# Sheet1.net
KiCad netlist of a schematic drawn in Altium Designer
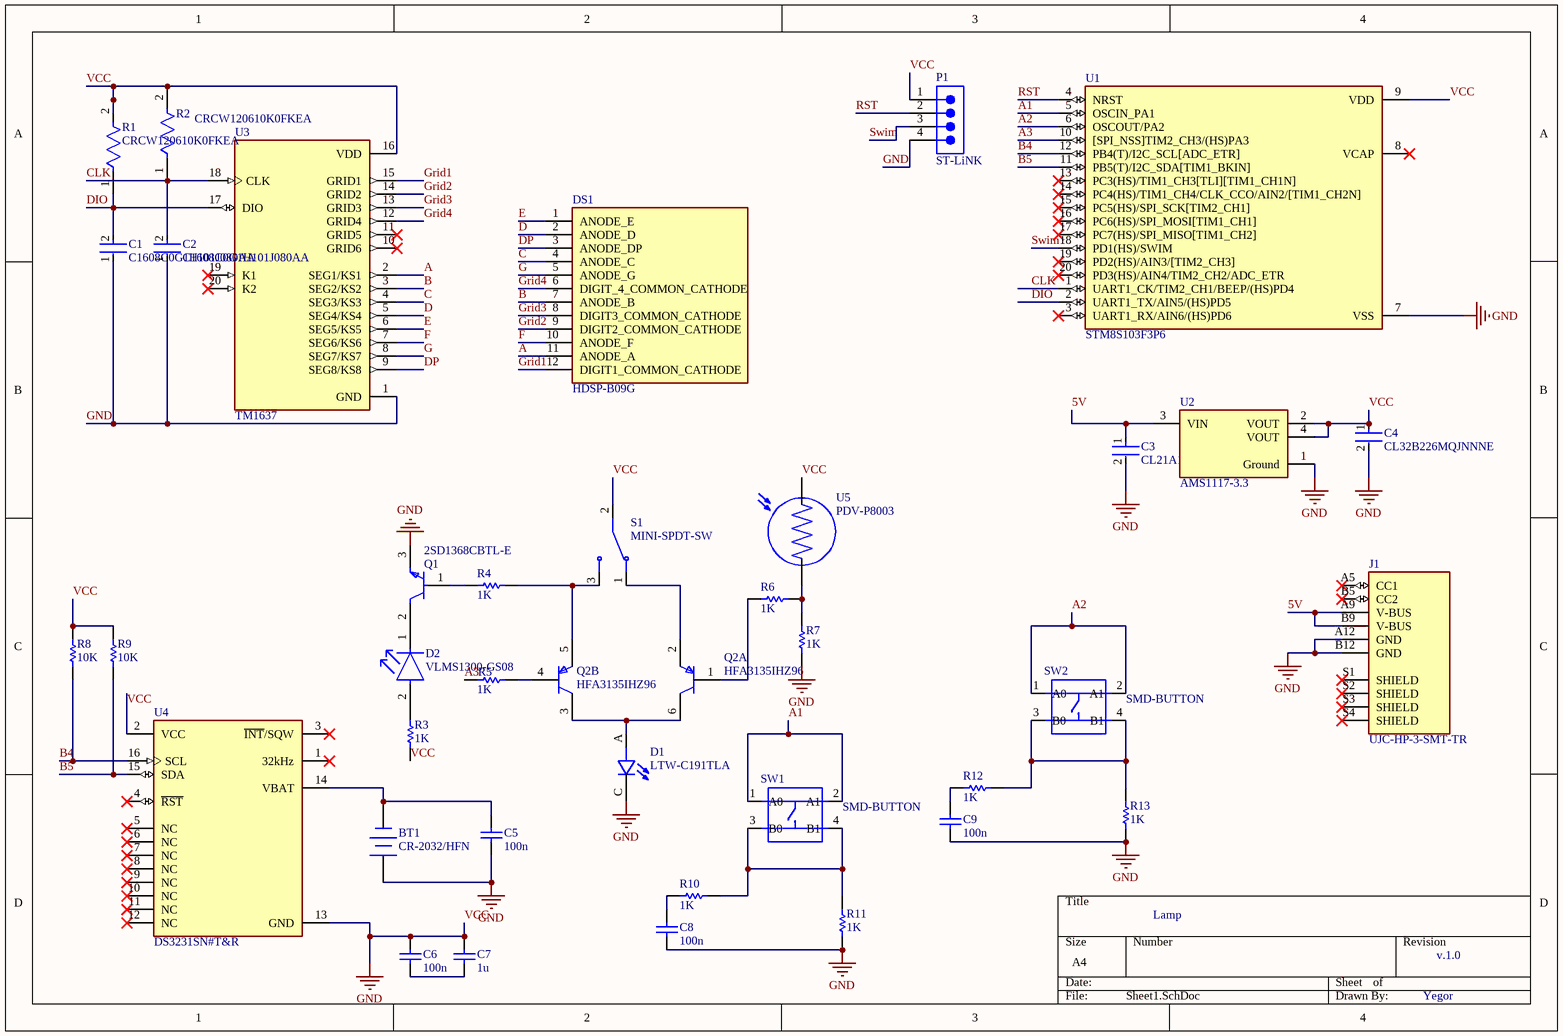
[diagram p0: Sheet1.SchDoc]

(export (version "E")
  (design (tool "Eeschema 10.0.6"))
  (components
    (comp (ref "BT1")
      (value "CR-2032/HFN")
      (footprint "PANA-CR-2032HFN")
      (description "Coin Cell Battery, 225 mAh, 0.2 mA, 3 V, -30 to 60 degC, Bulk")
      (fields (field (name "MANUFACTURER") "Panasonic"))
      (libsource (lib "Components - 25.08.25 - 13.52") (part "CMP-2000-05296-1"))
    )
    (comp (ref "C1")
      (value "C1608C0G1H101J080AA")
      (footprint "FP-C1608-080-0_1-MFG")
      (description "Multilayer Ceramic Capacitors 100pF ±5% 50V C0G SMD 0603")
      (fields (field (name "VOLTAGE") "50V") (field (name "TOLERANCE") "5%"))
      (libsource (lib "Components - 25.08.25 - 11.32") (part "CMP-08246-002637-1"))
    )
    (comp (ref "C2")
      (value "C1608C0G1H101J080AA")
      (footprint "FP-C1608-080-0_1-MFG")
      (description "Multilayer Ceramic Capacitors 100pF ±5% 50V C0G SMD 0603")
      (fields (field (name "VOLTAGE") "50V") (field (name "TOLERANCE") "5%"))
      (libsource (lib "Components - 25.08.25 - 11.32") (part "CMP-08246-002637-1"))
    )
    (comp (ref "C3")
      (value "CL21A106MPFNNNF")
      (footprint "FP-CL21-IPC_A")
      (description "CL21 Series 0805 10uF 10V ±20% Tolerance X5R Multilayer Ceramic Chip Capacitor")
      (fields (field (name "TOLERANCE") "20%"))
      (libsource (lib "Components - 25.08.25 - 12.18") (part "CMP-13271-002245-1"))
    )
    (comp (ref "C4")
      (value "CL32B226MQJNNNE")
      (footprint "FP-CL32-IPC_A")
      (description "Cap Ceramic 22uF 6.3V X7R ±20% SMD 1210 +125°C Embossed T/R")
      (fields (field (name "TOLERANCE") "20%"))
      (libsource (lib "Components - 25.08.25 - 12.17") (part "CMP-13271-001877-1"))
    )
    (comp (ref "C5")
      (value "100n")
      (description "Capacitor")
      (libsource (lib "Simulation Generic Components") (part "Capacitor"))
    )
    (comp (ref "C6")
      (value "100n")
      (description "Capacitor")
      (libsource (lib "Simulation Generic Components") (part "Capacitor"))
    )
    (comp (ref "C7")
      (value "1u")
      (description "Capacitor")
      (libsource (lib "Simulation Generic Components") (part "Capacitor"))
    )
    (comp (ref "C8")
      (value "100n")
      (description "Capacitor")
      (libsource (lib "Simulation Generic Components") (part "Capacitor"))
    )
    (comp (ref "C9")
      (value "100n")
      (description "Capacitor")
      (libsource (lib "Simulation Generic Components") (part "Capacitor"))
    )
    (comp (ref "D1")
      (value "LTW-C191TLA")
      (footprint "LEDC1608X65N")
      (description "CHIP LED WHITE 0603 TOP VIEW")
      (libsource (lib "LTW-C191TLA") (part "LTW-C191TLA"))
    )
    (comp (ref "D2")
      (value "VLMS1300-GS08")
      (footprint "FP-6_541-5092_01-4-MFG")
      (description "LED RED 0603 SMD")
      (fields
        (field (name "MANUFACTURER") "Vishay")
        (field (name "OCTOPART") "https://octopart.com/vlms1300-gs08-vishay-21709201")
      )
      (libsource (lib "Components - 25.08.25 - 21.29") (part "CMP-02520-000012-1"))
    )
    (comp (ref "DS1")
      (value "HDSP-B09G")
      (footprint "AVAGO_HDSP-B09G")
      (fields (field (name "MF") "Broadcom / Avago"))
      (libsource (lib "HDSP-B09G") (part "HDSP-B09G"))
    )
    (comp (ref "J1")
      (value "UJC-HP-3-SMT-TR")
      (footprint "CUI_UJC-HP-3-SMT-TR")
      (libsource (lib "UJC-HP-3-SMT-TR") (part "UJC-HP-3-SMT-TR"))
    )
    (comp (ref "P1")
      (value "ST-LiNK")
      (footprint "61300411021")
      (libsource (lib "Components - 25.08.25 - 11.48") (part "CMP-1502-01063-3"))
    )
    (comp (ref "Q1")
      (value "2SD1368CBTL-E")
      (footprint "PLZZ0004CA-A_MFG")
      (description "Trans GP BJT NPN 50V 1A 4-Pin(3+Tab) UPAK T/R")
      (libsource (lib "Components - 25.08.25 - 21.28") (part "CMP-00572-18697870-1"))
    )
    (comp (ref "Q2")
      (value "HFA3135IHZ96")
      (footprint "SOT95P280X145-6_P6_064_N")
      (description "Transistor, Bjt, Pair, Pnp, 11V V(Br)Ceo, 14Ma I(C), So")
      (libsource (lib "Components - 25.08.25 - 12.53") (part "CMP-00572-88253858-3"))
    )
    (comp (ref "R1")
      (value "CRCW120610K0FKEA")
      (footprint "FP-CRCW1206-e3-IPC_B")
      (description "RES Thick Film, 10kΩ, 1%, 0.25W, 100ppm/°C, 1206")
      (fields (field (name "TOLERANCE") "1%"))
      (libsource (lib "Components - 25.08.25 - 11.27") (part "CMP-2003-04807-2"))
    )
    (comp (ref "R2")
      (value "CRCW120610K0FKEA")
      (footprint "FP-CRCW1206-e3-IPC_B")
      (description "RES Thick Film, 10kΩ, 1%, 0.25W, 100ppm/°C, 1206")
      (fields (field (name "TOLERANCE") "1%"))
      (libsource (lib "Components - 25.08.25 - 11.27") (part "CMP-2003-04807-2"))
    )
    (comp (ref "R3")
      (value "1K")
      (description "Resistor")
      (libsource (lib "Simulation Generic Components") (part "Resistor"))
    )
    (comp (ref "R4")
      (value "1K")
      (description "Resistor")
      (libsource (lib "Simulation Generic Components") (part "Resistor"))
    )
    (comp (ref "R5")
      (value "1K")
      (description "Resistor")
      (libsource (lib "Simulation Generic Components") (part "Resistor"))
    )
    (comp (ref "R6")
      (value "1K")
      (description "Resistor")
      (libsource (lib "Simulation Generic Components") (part "Resistor"))
    )
    (comp (ref "R7")
      (value "1K")
      (description "Resistor")
      (libsource (lib "Simulation Generic Components") (part "Resistor"))
    )
    (comp (ref "R8")
      (value "10K")
      (description "Resistor")
      (libsource (lib "Simulation Generic Components") (part "Resistor"))
    )
    (comp (ref "R9")
      (value "10K")
      (description "Resistor")
      (libsource (lib "Simulation Generic Components") (part "Resistor"))
    )
    (comp (ref "R10")
      (value "1K")
      (description "Resistor")
      (libsource (lib "Simulation Generic Components") (part "Resistor"))
    )
    (comp (ref "R11")
      (value "1K")
      (description "Resistor")
      (libsource (lib "Simulation Generic Components") (part "Resistor"))
    )
    (comp (ref "R12")
      (value "1K")
      (description "Resistor")
      (libsource (lib "Simulation Generic Components") (part "Resistor"))
    )
    (comp (ref "R13")
      (value "1K")
      (description "Resistor")
      (libsource (lib "Simulation Generic Components") (part "Resistor"))
    )
    (comp (ref "S1")
      (value "MINI-SPDT-SW")
      (footprint "SW_MINI-SPDT-SW")
      (libsource (lib "MINI-SPDT-SW") (part "MINI-SPDT-SW"))
    )
    (comp (ref "SW1")
      (value "SMD-BUTTON")
      (footprint "SW4-SMD-5.2X5.2X1.5MM")
      (description "Switch Tactile N.O. SPST Button Gull Wing 0.05A 12VDC 3.43N SMD T/R")
      (fields (field (name "MF") "ALPS") (field (name "MP") "SKQGAKE010"))
      (libsource (lib "SMD-BUTTON_4P-5.2X5.2X1.5MM-SKQGAKE010_") (part "SMD-BUTTON(4P-5.2X5.2X1.5MM-SKQGAKE010)"))
    )
    (comp (ref "SW2")
      (value "SMD-BUTTON")
      (footprint "SW4-SMD-5.2X5.2X1.5MM")
      (description "Switch Tactile N.O. SPST Button Gull Wing 0.05A 12VDC 3.43N SMD T/R")
      (fields (field (name "MF") "ALPS") (field (name "MP") "SKQGAKE010"))
      (libsource (lib "SMD-BUTTON_4P-5.2X5.2X1.5MM-SKQGAKE010_") (part "SMD-BUTTON(4P-5.2X5.2X1.5MM-SKQGAKE010)"))
    )
    (comp (ref "U1")
      (value "STM8S103F3P6")
      (footprint "SOP65P640X120-20N")
      (description "STM8 series Microcontroller IC 8-Bit 16MHz 8KB (8K x 8) FLASH 20-TSSOP")
      (fields (field (name "MF") "STMicroelectronics"))
      (libsource (lib "STM8S103F3P6") (part "STM8S103F3P6"))
    )
    (comp (ref "U2")
      (value "AMS1117-3.3")
      (footprint "FP-AMS1117-IPC_A")
      (description "LDO Voltage Regulators 1A, 3.3V")
      (fields
        (field (name "OCTOPART") "https://octopart.com/ams1117-3.3-advanced+monolithic+systems-25899300")
        (field (name "MANUFACTURER") "Advanced Monolithic Systems")
      )
      (libsource (lib "Components - 25.08.25 - 12.03") (part "CMP-209535-000001-1"))
    )
    (comp (ref "U3")
      (value "TM1637")
      (footprint "DIP778W43P254L2612H431Q20N")
      (description "LED Drive Control Special Circuit")
      (fields (field (name "MF") "Titan Micro Electronics"))
      (libsource (lib "TM1637") (part "TM1637"))
    )
    (comp (ref "U4")
      (value "DS3231SN#T&R")
      (footprint "FP-W16-H2-MFG")
      (description "IC RTC CLK/CALENDAR I2C 16-SOIC")
      (libsource (lib "Components - 25.08.25 - 13.49") (part "CMP-0254-00375-2"))
    )
    (comp (ref "U5")
      (value "PDV-P8003")
      (footprint "XDCR_PDV-P8003")
      (description "CdS Cells 520nm 16 ~ 33kOhms @ 10 lux")
      (fields (field (name "MF") "Advanced Photonix"))
      (libsource (lib "PDV-P8003") (part "PDV-P8003"))
    )
  )
  (nets
    (net (code "1") (name "/5V") (class "Default")
      (node (ref "C3") (pin "1") (pinfunction "1_1") (pintype "passive"))
      (node (ref "J1") (pin "A9") (pinfunction "V-BUS_A9") (pintype "power_in"))
      (node (ref "J1") (pin "B9") (pinfunction "V-BUS_B9") (pintype "power_in"))
      (node (ref "U2") (pin "3") (pinfunction "VIN_3") (pintype "power_in"))
    )
    (net (code "2") (name "/A") (class "Default")
      (node (ref "DS1") (pin "11") (pinfunction "ANODE_A_11") (pintype "passive"))
      (node (ref "U3") (pin "2") (pinfunction "SEG1/KS1_2") (pintype "output"))
    )
    (net (code "3") (name "/A1") (class "Default")
      (node (ref "SW1") (pin "1") (pinfunction "A0_1") (pintype "bidirectional"))
      (node (ref "SW1") (pin "2") (pinfunction "A1_2") (pintype "bidirectional"))
      (node (ref "U1") (pin "5") (pinfunction "OSCIN_PA1_5") (pintype "bidirectional"))
    )
    (net (code "4") (name "/A2") (class "Default")
      (node (ref "SW2") (pin "1") (pinfunction "A0_1") (pintype "bidirectional"))
      (node (ref "SW2") (pin "2") (pinfunction "A1_2") (pintype "bidirectional"))
      (node (ref "U1") (pin "6") (pinfunction "OSCOUT/PA2_6") (pintype "bidirectional"))
    )
    (net (code "5") (name "/A3") (class "Default")
      (node (ref "R5") (pin "2") (pinfunction "2_2") (pintype "passive"))
      (node (ref "U1") (pin "10") (pinfunction "[SPI_NSS]TIM2_CH3/(HS)PA3_10") (pintype "bidirectional"))
    )
    (net (code "6") (name "/B") (class "Default")
      (node (ref "DS1") (pin "7") (pinfunction "ANODE_B_7") (pintype "passive"))
      (node (ref "U3") (pin "3") (pinfunction "SEG2/KS2_3") (pintype "output"))
    )
    (net (code "7") (name "/B4") (class "Default")
      (node (ref "R8") (pin "1") (pinfunction "1_1") (pintype "passive"))
      (node (ref "U1") (pin "12") (pinfunction "PB4(T)/I2C_SCL[ADC_ETR]_12") (pintype "bidirectional"))
      (node (ref "U4") (pin "16") (pinfunction "SCL_16") (pintype "input"))
    )
    (net (code "8") (name "/B5") (class "Default")
      (node (ref "R9") (pin "1") (pinfunction "1_1") (pintype "passive"))
      (node (ref "U1") (pin "11") (pinfunction "PB5(T)/I2C_SDA[TIM1_BKIN]_11") (pintype "bidirectional"))
      (node (ref "U4") (pin "15") (pinfunction "SDA_15") (pintype "bidirectional"))
    )
    (net (code "9") (name "/C") (class "Default")
      (node (ref "DS1") (pin "4") (pinfunction "ANODE_C_4") (pintype "passive"))
      (node (ref "U3") (pin "4") (pinfunction "SEG3/KS3_4") (pintype "output"))
    )
    (net (code "10") (name "/CLK") (class "Default")
      (node (ref "C2") (pin "2") (pinfunction "2_2") (pintype "passive"))
      (node (ref "R2") (pin "1") (pinfunction "1_1") (pintype "passive"))
      (node (ref "U1") (pin "1") (pinfunction "UART1_CK/TIM2_CH1/BEEP/(HS)PD4_1") (pintype "bidirectional"))
      (node (ref "U3") (pin "18") (pinfunction "CLK_18") (pintype "input"))
    )
    (net (code "11") (name "/D") (class "Default")
      (node (ref "DS1") (pin "2") (pinfunction "ANODE_D_2") (pintype "passive"))
      (node (ref "U3") (pin "5") (pinfunction "SEG4/KS4_5") (pintype "output"))
    )
    (net (code "12") (name "/DIO") (class "Default")
      (node (ref "C1") (pin "2") (pinfunction "2_2") (pintype "passive"))
      (node (ref "R1") (pin "1") (pinfunction "1_1") (pintype "passive"))
      (node (ref "U1") (pin "2") (pinfunction "UART1_TX/AIN5/(HS)PD5_2") (pintype "bidirectional"))
      (node (ref "U3") (pin "17") (pinfunction "DIO_17") (pintype "bidirectional"))
    )
    (net (code "13") (name "/DP") (class "Default")
      (node (ref "DS1") (pin "3") (pinfunction "ANODE_DP_3") (pintype "passive"))
      (node (ref "U3") (pin "9") (pinfunction "SEG8/KS8_9") (pintype "output"))
    )
    (net (code "14") (name "/E") (class "Default")
      (node (ref "DS1") (pin "1") (pinfunction "ANODE_E_1") (pintype "passive"))
      (node (ref "U3") (pin "6") (pinfunction "SEG5/KS5_6") (pintype "output"))
    )
    (net (code "15") (name "/F") (class "Default")
      (node (ref "DS1") (pin "10") (pinfunction "ANODE_F_10") (pintype "passive"))
      (node (ref "U3") (pin "7") (pinfunction "SEG6/KS6_7") (pintype "output"))
    )
    (net (code "16") (name "/G") (class "Default")
      (node (ref "DS1") (pin "5") (pinfunction "ANODE_G_5") (pintype "passive"))
      (node (ref "U3") (pin "8") (pinfunction "SEG7/KS7_8") (pintype "output"))
    )
    (net (code "17") (name "/Grid1") (class "Default")
      (node (ref "DS1") (pin "12") (pinfunction "DIGIT1_COMMON_CATHODE_12") (pintype "passive"))
      (node (ref "U3") (pin "15") (pinfunction "GRID1_15") (pintype "output"))
    )
    (net (code "18") (name "/Grid2") (class "Default")
      (node (ref "DS1") (pin "9") (pinfunction "DIGIT2_COMMON_CATHODE_9") (pintype "passive"))
      (node (ref "U3") (pin "14") (pinfunction "GRID2_14") (pintype "output"))
    )
    (net (code "19") (name "/Grid3") (class "Default")
      (node (ref "DS1") (pin "8") (pinfunction "DIGIT3_COMMON_CATHODE_8") (pintype "passive"))
      (node (ref "U3") (pin "13") (pinfunction "GRID3_13") (pintype "output"))
    )
    (net (code "20") (name "/Grid4") (class "Default")
      (node (ref "DS1") (pin "6") (pinfunction "DIGIT_4_COMMON_CATHODE_6") (pintype "passive"))
      (node (ref "U3") (pin "12") (pinfunction "GRID4_12") (pintype "output"))
    )
    (net (code "21") (name "/RST") (class "Default")
      (node (ref "P1") (pin "2") (pinfunction "2_2") (pintype "passive"))
      (node (ref "U1") (pin "4") (pinfunction "NRST_4") (pintype "bidirectional"))
    )
    (net (code "22") (name "/Swim") (class "Default")
      (node (ref "P1") (pin "3") (pinfunction "3_3") (pintype "passive"))
      (node (ref "U1") (pin "18") (pinfunction "PD1(HS)/SWIM_18") (pintype "bidirectional"))
    )
    (net (code "23") (name "GND") (class "Default")
      (node (ref "BT1") (pin "1") (pinfunction "+_1") (pintype "passive"))
      (node (ref "C1") (pin "1") (pinfunction "1_1") (pintype "passive"))
      (node (ref "C2") (pin "1") (pinfunction "1_1") (pintype "passive"))
      (node (ref "C3") (pin "2") (pinfunction "2_2") (pintype "passive"))
      (node (ref "C4") (pin "1") (pinfunction "1_1") (pintype "passive"))
      (node (ref "C4") (pin "2") (pinfunction "2_2") (pintype "passive"))
      (node (ref "C5") (pin "1") (pinfunction "1_1") (pintype "passive"))
      (node (ref "C6") (pin "2") (pinfunction "2_2") (pintype "passive"))
      (node (ref "C7") (pin "2") (pinfunction "2_2") (pintype "passive"))
      (node (ref "C8") (pin "1") (pinfunction "1_1") (pintype "passive"))
      (node (ref "C9") (pin "1") (pinfunction "1_1") (pintype "passive"))
      (node (ref "D1") (pin "C") (pinfunction "C_C") (pintype "passive"))
      (node (ref "J1") (pin "A12") (pinfunction "GND_A12") (pintype "power_in"))
      (node (ref "J1") (pin "B12") (pinfunction "GND_B12") (pintype "power_in"))
      (node (ref "P1") (pin "1") (pinfunction "1_1") (pintype "passive"))
      (node (ref "P1") (pin "4") (pinfunction "4_4") (pintype "passive"))
      (node (ref "Q1") (pin "3") (pinfunction "EMITTER_3") (pintype "passive"))
      (node (ref "R1") (pin "2") (pinfunction "2_2") (pintype "passive"))
      (node (ref "R11") (pin "1") (pinfunction "1_1") (pintype "passive"))
      (node (ref "R13") (pin "1") (pinfunction "1_1") (pintype "passive"))
      (node (ref "R2") (pin "2") (pinfunction "2_2") (pintype "passive"))
      (node (ref "R3") (pin "1") (pinfunction "1_1") (pintype "passive"))
      (node (ref "R7") (pin "1") (pinfunction "1_1") (pintype "passive"))
      (node (ref "R8") (pin "2") (pinfunction "2_2") (pintype "passive"))
      (node (ref "R9") (pin "2") (pinfunction "2_2") (pintype "passive"))
      (node (ref "S1") (pin "2") (pinfunction "2_2") (pintype "passive"))
      (node (ref "U1") (pin "7") (pinfunction "VSS_7") (pintype "power_in"))
      (node (ref "U1") (pin "9") (pinfunction "VDD_9") (pintype "power_in"))
      (node (ref "U2") (pin "1") (pinfunction "Ground_1") (pintype "power_in"))
      (node (ref "U2") (pin "2") (pinfunction "VOUT_2") (pintype "passive"))
      (node (ref "U2") (pin "4") (pinfunction "VOUT_4") (pintype "passive"))
      (node (ref "U3") (pin "1") (pinfunction "GND_1") (pintype "power_in"))
      (node (ref "U3") (pin "16") (pinfunction "VDD_16") (pintype "power_in"))
      (node (ref "U4") (pin "13") (pinfunction "GND_13") (pintype "power_in"))
      (node (ref "U4") (pin "2") (pinfunction "VCC_2") (pintype "power_in"))
      (node (ref "U5") (pin "2") (pinfunction "2_2") (pintype "passive"))
    )
    (net (code "24") (name "Net-(BT1--)") (class "Default")
      (node (ref "BT1") (pin "2") (pinfunction "-_2") (pintype "passive"))
      (node (ref "C5") (pin "2") (pinfunction "2_2") (pintype "passive"))
      (node (ref "U4") (pin "14") (pinfunction "VBAT_14") (pintype "power_in"))
    )
    (net (code "25") (name "Net-(C6-Pad1)") (class "Default")
      (node (ref "C6") (pin "1") (pinfunction "1_1") (pintype "passive"))
      (node (ref "C7") (pin "1") (pinfunction "1_1") (pintype "passive"))
    )
    (net (code "26") (name "Net-(C8-Pad2)") (class "Default")
      (node (ref "C8") (pin "2") (pinfunction "2_2") (pintype "passive"))
      (node (ref "R10") (pin "1") (pinfunction "1_1") (pintype "passive"))
    )
    (net (code "27") (name "Net-(C9-Pad2)") (class "Default")
      (node (ref "C9") (pin "2") (pinfunction "2_2") (pintype "passive"))
      (node (ref "R12") (pin "1") (pinfunction "1_1") (pintype "passive"))
    )
    (net (code "28") (name "Net-(D2-A)") (class "Default")
      (node (ref "D2") (pin "2") (pinfunction "A_2") (pintype "passive"))
      (node (ref "R3") (pin "2") (pinfunction "2_2") (pintype "passive"))
    )
    (net (code "29") (name "Net-(D2-C)") (class "Default")
      (node (ref "D2") (pin "1") (pinfunction "C_1") (pintype "passive"))
      (node (ref "Q1") (pin "2") (pinfunction "COLLECTOR_2") (pintype "passive"))
    )
    (net (code "30") (name "Net-(Q1-BASE)") (class "Default")
      (node (ref "Q1") (pin "1") (pinfunction "BASE_1") (pintype "passive"))
      (node (ref "R4") (pin "1") (pinfunction "1_1") (pintype "passive"))
    )
    (net (code "31") (name "Net-(Q2A-1_BASE)") (class "Default")
      (node (ref "Q2") (pin "1") (pinfunction "1_BASE_1") (pintype "passive"))
      (node (ref "R6") (pin "1") (pinfunction "1_1") (pintype "passive"))
    )
    (net (code "32") (name "Net-(Q2A-1_COLLECTOR)") (class "Default")
      (node (ref "D1") (pin "A") (pinfunction "A_A") (pintype "passive"))
      (node (ref "Q2") (pin "3") (pinfunction "2_COLLECTOR_3") (pintype "passive"))
      (node (ref "Q2") (pin "6") (pinfunction "1_COLLECTOR_6") (pintype "passive"))
    )
    (net (code "33") (name "Net-(Q2A-1_EMITTER)") (class "Default")
      (node (ref "Q2") (pin "2") (pinfunction "1_EMITTER_2") (pintype "passive"))
      (node (ref "S1") (pin "1") (pinfunction "1_1") (pintype "passive"))
    )
    (net (code "34") (name "Net-(Q2B-2_BASE)") (class "Default")
      (node (ref "Q2") (pin "4") (pinfunction "2_BASE_4") (pintype "passive"))
      (node (ref "R5") (pin "1") (pinfunction "1_1") (pintype "passive"))
    )
    (net (code "35") (name "Net-(Q2B-2_EMITTER)") (class "Default")
      (node (ref "Q2") (pin "5") (pinfunction "2_EMITTER_5") (pintype "passive"))
      (node (ref "R4") (pin "2") (pinfunction "2_2") (pintype "passive"))
      (node (ref "S1") (pin "3") (pinfunction "3_3") (pintype "passive"))
    )
    (net (code "36") (name "Net-(R6-Pad2)") (class "Default")
      (node (ref "R6") (pin "2") (pinfunction "2_2") (pintype "passive"))
      (node (ref "R7") (pin "2") (pinfunction "2_2") (pintype "passive"))
      (node (ref "U5") (pin "1") (pinfunction "1_1") (pintype "passive"))
    )
    (net (code "37") (name "Net-(SW1-B0)") (class "Default")
      (node (ref "R10") (pin "2") (pinfunction "2_2") (pintype "passive"))
      (node (ref "R11") (pin "2") (pinfunction "2_2") (pintype "passive"))
      (node (ref "SW1") (pin "3") (pinfunction "B0_3") (pintype "bidirectional"))
      (node (ref "SW1") (pin "4") (pinfunction "B1_4") (pintype "bidirectional"))
    )
    (net (code "38") (name "Net-(SW2-B0)") (class "Default")
      (node (ref "R12") (pin "2") (pinfunction "2_2") (pintype "passive"))
      (node (ref "R13") (pin "2") (pinfunction "2_2") (pintype "passive"))
      (node (ref "SW2") (pin "3") (pinfunction "B0_3") (pintype "bidirectional"))
      (node (ref "SW2") (pin "4") (pinfunction "B1_4") (pintype "bidirectional"))
    )
    (net (code "39") (name "unconnected-(J1-CC1-PadA5)") (class "Default")
      (node (ref "J1") (pin "A5") (pinfunction "CC1_A5") (pintype "bidirectional+no_connect"))
    )
    (net (code "40") (name "unconnected-(J1-CC2-PadB5)") (class "Default")
      (node (ref "J1") (pin "B5") (pinfunction "CC2_B5") (pintype "bidirectional+no_connect"))
    )
    (net (code "41") (name "unconnected-(J1-SHIELD-PadS1)") (class "Default")
      (node (ref "J1") (pin "S1") (pinfunction "SHIELD_S1") (pintype "passive+no_connect"))
    )
    (net (code "42") (name "unconnected-(J1-SHIELD-PadS2)") (class "Default")
      (node (ref "J1") (pin "S2") (pinfunction "SHIELD_S2") (pintype "passive+no_connect"))
    )
    (net (code "43") (name "unconnected-(J1-SHIELD-PadS3)") (class "Default")
      (node (ref "J1") (pin "S3") (pinfunction "SHIELD_S3") (pintype "passive+no_connect"))
    )
    (net (code "44") (name "unconnected-(J1-SHIELD-PadS4)") (class "Default")
      (node (ref "J1") (pin "S4") (pinfunction "SHIELD_S4") (pintype "passive+no_connect"))
    )
    (net (code "45") (name "unconnected-(U1-PC3(HS){slash}TIM1_CH3[TLI][TIM1_CH1N]-Pad13)") (class "Default")
      (node (ref "U1") (pin "13") (pinfunction "PC3(HS)/TIM1_CH3[TLI][TIM1_CH1N]_13") (pintype "bidirectional+no_connect"))
    )
    (net (code "46") (name "unconnected-(U1-PC4(HS){slash}TIM1_CH4{slash}CLK_CCO{slash}AIN2{slash}[TIM1_CH2N]-Pad14)") (class "Default")
      (node (ref "U1") (pin "14") (pinfunction "PC4(HS)/TIM1_CH4/CLK_CCO/AIN2/[TIM1_CH2N]_14") (pintype "bidirectional+no_connect"))
    )
    (net (code "47") (name "unconnected-(U1-PC5(HS){slash}SPI_SCK[TIM2_CH1]-Pad15)") (class "Default")
      (node (ref "U1") (pin "15") (pinfunction "PC5(HS)/SPI_SCK[TIM2_CH1]_15") (pintype "bidirectional+no_connect"))
    )
    (net (code "48") (name "unconnected-(U1-PC6(HS){slash}SPI_MOSI[TIM1_CH1]-Pad16)") (class "Default")
      (node (ref "U1") (pin "16") (pinfunction "PC6(HS)/SPI_MOSI[TIM1_CH1]_16") (pintype "bidirectional+no_connect"))
    )
    (net (code "49") (name "unconnected-(U1-PC7(HS){slash}SPI_MISO[TIM1_CH2]-Pad17)") (class "Default")
      (node (ref "U1") (pin "17") (pinfunction "PC7(HS)/SPI_MISO[TIM1_CH2]_17") (pintype "bidirectional+no_connect"))
    )
    (net (code "50") (name "unconnected-(U1-PD2(HS){slash}AIN3{slash}[TIM2_CH3]-Pad19)") (class "Default")
      (node (ref "U1") (pin "19") (pinfunction "PD2(HS)/AIN3/[TIM2_CH3]_19") (pintype "bidirectional+no_connect"))
    )
    (net (code "51") (name "unconnected-(U1-PD3(HS){slash}AIN4{slash}TIM2_CH2{slash}ADC_ETR-Pad20)") (class "Default")
      (node (ref "U1") (pin "20") (pinfunction "PD3(HS)/AIN4/TIM2_CH2/ADC_ETR_20") (pintype "bidirectional+no_connect"))
    )
    (net (code "52") (name "unconnected-(U1-UART1_RX{slash}AIN6{slash}(HS)PD6-Pad3)") (class "Default")
      (node (ref "U1") (pin "3") (pinfunction "UART1_RX/AIN6/(HS)PD6_3") (pintype "bidirectional+no_connect"))
    )
    (net (code "53") (name "unconnected-(U1-VCAP-Pad8)") (class "Default")
      (node (ref "U1") (pin "8") (pinfunction "VCAP_8") (pintype "passive+no_connect"))
    )
    (net (code "54") (name "unconnected-(U3-GRID5-Pad11)") (class "Default")
      (node (ref "U3") (pin "11") (pinfunction "GRID5_11") (pintype "output+no_connect"))
    )
    (net (code "55") (name "unconnected-(U3-GRID6-Pad10)") (class "Default")
      (node (ref "U3") (pin "10") (pinfunction "GRID6_10") (pintype "output+no_connect"))
    )
    (net (code "56") (name "unconnected-(U3-K1-Pad19)") (class "Default")
      (node (ref "U3") (pin "19") (pinfunction "K1_19") (pintype "input+no_connect"))
    )
    (net (code "57") (name "unconnected-(U3-K2-Pad20)") (class "Default")
      (node (ref "U3") (pin "20") (pinfunction "K2_20") (pintype "input+no_connect"))
    )
    (net (code "58") (name "unconnected-(U4-32kHz-Pad1)") (class "Default")
      (node (ref "U4") (pin "1") (pinfunction "32kHz_1") (pintype "open_collector+no_connect"))
    )
    (net (code "59") (name "unconnected-(U4-NC-Pad5)") (class "Default")
      (node (ref "U4") (pin "5") (pinfunction "NC_5") (pintype "passive+no_connect"))
    )
    (net (code "60") (name "unconnected-(U4-NC-Pad6)") (class "Default")
      (node (ref "U4") (pin "6") (pinfunction "NC_6") (pintype "passive+no_connect"))
    )
    (net (code "61") (name "unconnected-(U4-NC-Pad7)") (class "Default")
      (node (ref "U4") (pin "7") (pinfunction "NC_7") (pintype "passive+no_connect"))
    )
    (net (code "62") (name "unconnected-(U4-NC-Pad8)") (class "Default")
      (node (ref "U4") (pin "8") (pinfunction "NC_8") (pintype "passive+no_connect"))
    )
    (net (code "63") (name "unconnected-(U4-NC-Pad9)") (class "Default")
      (node (ref "U4") (pin "9") (pinfunction "NC_9") (pintype "passive+no_connect"))
    )
    (net (code "64") (name "unconnected-(U4-NC-Pad10)") (class "Default")
      (node (ref "U4") (pin "10") (pinfunction "NC_10") (pintype "passive+no_connect"))
    )
    (net (code "65") (name "unconnected-(U4-NC-Pad11)") (class "Default")
      (node (ref "U4") (pin "11") (pinfunction "NC_11") (pintype "passive+no_connect"))
    )
    (net (code "66") (name "unconnected-(U4-NC-Pad12)") (class "Default")
      (node (ref "U4") (pin "12") (pinfunction "NC_12") (pintype "passive+no_connect"))
    )
    (net (code "67") (name "unconnected-(U4-~{INT}{slash}SQW-Pad3)") (class "Default")
      (node (ref "U4") (pin "3") (pinfunction "~{INT}/SQW_3") (pintype "open_collector+no_connect"))
    )
    (net (code "68") (name "unconnected-(U4-~{RST}-Pad4)") (class "Default")
      (node (ref "U4") (pin "4") (pinfunction "~{RST}_4") (pintype "bidirectional+no_connect"))
    )
  )
)
